# pic32_dip_breakout.net
KiCad netlist of a schematic drawn in EAGLE
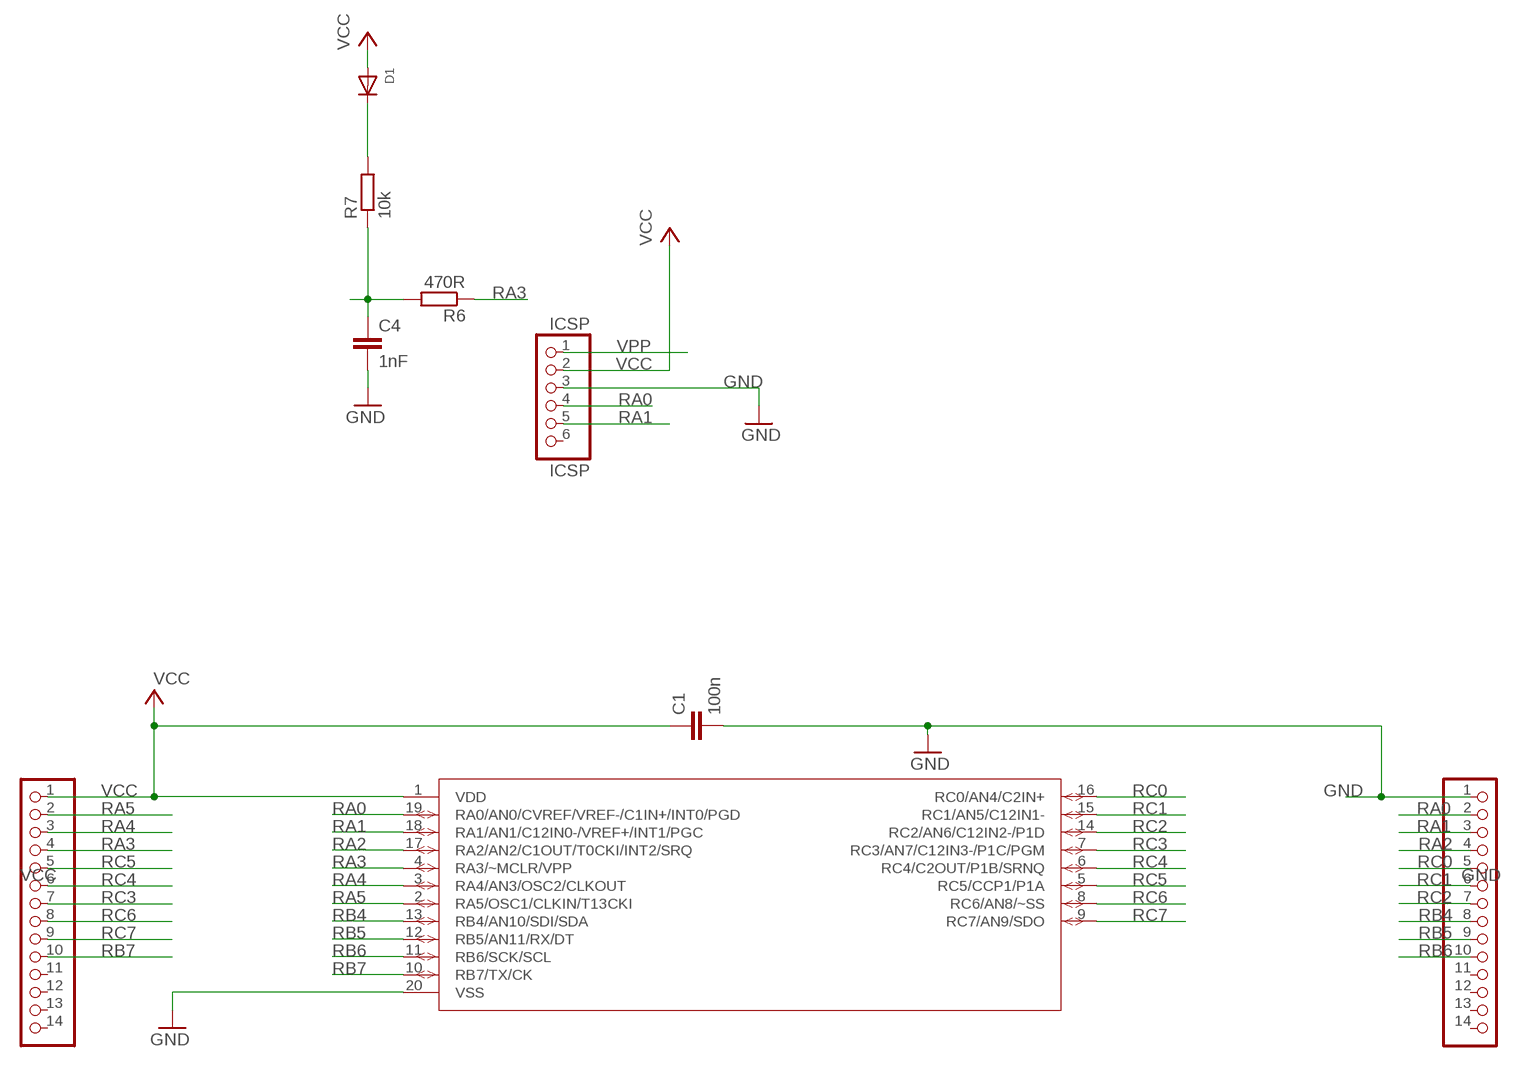
[diagram p0: schematic, sheet 1]

(export (version "E")
  (design (tool "Eeschema 10.0.6"))
  (components
    (comp (ref "C1")
      (value "100n")
      (footprint "eagle-import:C0805")
      (libsource (lib "eagle-import") (part "C-EUC0805"))
    )
    (comp (ref "C4")
      (value "1nF")
      (footprint "eagle-import:C0805")
      (libsource (lib "eagle-import") (part "resistor_C-EUC0805"))
    )
    (comp (ref "D1")
      (value "DIODESOD-323F")
      (footprint "eagle-import:SOD-323F")
      (libsource (lib "eagle-import") (part "DIODESOD-323F"))
    )
    (comp (ref "GND")
      (value "PINHD-1X14")
      (footprint "eagle-import:1X14")
      (libsource (lib "eagle-import") (part "PINHD-1X14"))
    )
    (comp (ref "ICSP")
      (value "ICSP")
      (footprint "eagle-import:1X06")
      (libsource (lib "eagle-import") (part "PINHD-1X6"))
    )
    (comp (ref "R6")
      (value "470R")
      (footprint "eagle-import:R0805")
      (libsource (lib "eagle-import") (part "R-EU_R0805"))
    )
    (comp (ref "R7")
      (value "10k")
      (footprint "eagle-import:R0805")
      (libsource (lib "eagle-import") (part "R-EU_R0805"))
    )
    (comp (ref "U$1")
      (value "PIC18F14K22-I/P")
      (footprint "eagle-import:DIP254P762X533-20")
      (fields (field (name "MPN") "PIC18F14k22-I/P"))
      (libsource (lib "eagle-import") (part "PIC18F14K22-I/P"))
    )
    (comp (ref "VCC")
      (value "PINHD-1X14")
      (footprint "eagle-import:1X14")
      (libsource (lib "eagle-import") (part "PINHD-1X14"))
    )
  )
  (nets
    (net (code "1") (name "/RA0") (class "Default")
      (node (ref "GND") (pin "2") (pinfunction "2_2") (pintype "passive"))
      (node (ref "ICSP") (pin "4") (pinfunction "4_4") (pintype "passive"))
      (node (ref "U$1") (pin "19") (pinfunction "RA0/AN0/CVREF/VREF-/C1IN+/INT0/PGD_19") (pintype "bidirectional"))
    )
    (net (code "2") (name "/RA1") (class "Default")
      (node (ref "GND") (pin "3") (pinfunction "3_3") (pintype "passive"))
      (node (ref "ICSP") (pin "5") (pinfunction "5_5") (pintype "passive"))
      (node (ref "U$1") (pin "18") (pinfunction "RA1/AN1/C12IN0-/VREF+/INT1/PGC_18") (pintype "bidirectional"))
    )
    (net (code "3") (name "/RA2") (class "Default")
      (node (ref "GND") (pin "4") (pinfunction "4_4") (pintype "passive"))
      (node (ref "U$1") (pin "17") (pinfunction "RA2/AN2/C1OUT/T0CKI/INT2/SRQ_17") (pintype "bidirectional"))
    )
    (net (code "4") (name "/RA3") (class "Default")
      (node (ref "R6") (pin "1") (pinfunction "1_1") (pintype "passive"))
      (node (ref "U$1") (pin "4") (pinfunction "RA3/~{MCLR/VPP}_4") (pintype "bidirectional"))
      (node (ref "VCC") (pin "4") (pinfunction "4_4") (pintype "passive"))
    )
    (net (code "5") (name "/RA4") (class "Default")
      (node (ref "U$1") (pin "3") (pinfunction "RA4/AN3/OSC2/CLKOUT_3") (pintype "bidirectional"))
      (node (ref "VCC") (pin "3") (pinfunction "3_3") (pintype "passive"))
    )
    (net (code "6") (name "/RA5") (class "Default")
      (node (ref "U$1") (pin "2") (pinfunction "RA5/OSC1/CLKIN/T13CKI_2") (pintype "bidirectional"))
      (node (ref "VCC") (pin "2") (pinfunction "2_2") (pintype "passive"))
    )
    (net (code "7") (name "/RB4") (class "Default")
      (node (ref "GND") (pin "8") (pinfunction "8_8") (pintype "passive"))
      (node (ref "U$1") (pin "13") (pinfunction "RB4/AN10/SDI/SDA_13") (pintype "bidirectional"))
    )
    (net (code "8") (name "/RB5") (class "Default")
      (node (ref "GND") (pin "9") (pinfunction "9_9") (pintype "passive"))
      (node (ref "U$1") (pin "12") (pinfunction "RB5/AN11/RX/DT_12") (pintype "bidirectional"))
    )
    (net (code "9") (name "/RB6") (class "Default")
      (node (ref "GND") (pin "10") (pinfunction "10_10") (pintype "passive"))
      (node (ref "U$1") (pin "11") (pinfunction "RB6/SCK/SCL_11") (pintype "bidirectional"))
    )
    (net (code "10") (name "/RB7") (class "Default")
      (node (ref "U$1") (pin "10") (pinfunction "RB7/TX/CK_10") (pintype "bidirectional"))
      (node (ref "VCC") (pin "10") (pinfunction "10_10") (pintype "passive"))
    )
    (net (code "11") (name "/RC0") (class "Default")
      (node (ref "GND") (pin "5") (pinfunction "5_5") (pintype "passive"))
      (node (ref "U$1") (pin "16") (pinfunction "RC0/AN4/C2IN+_16") (pintype "bidirectional"))
    )
    (net (code "12") (name "/RC1") (class "Default")
      (node (ref "GND") (pin "6") (pinfunction "6_6") (pintype "passive"))
      (node (ref "U$1") (pin "15") (pinfunction "RC1/AN5/C12IN1-_15") (pintype "bidirectional"))
    )
    (net (code "13") (name "/RC2") (class "Default")
      (node (ref "GND") (pin "7") (pinfunction "7_7") (pintype "passive"))
      (node (ref "U$1") (pin "14") (pinfunction "RC2/AN6/C12IN2-/P1D_14") (pintype "bidirectional"))
    )
    (net (code "14") (name "/RC3") (class "Default")
      (node (ref "U$1") (pin "7") (pinfunction "RC3/AN7/C12IN3-/P1C/PGM_7") (pintype "bidirectional"))
      (node (ref "VCC") (pin "7") (pinfunction "7_7") (pintype "passive"))
    )
    (net (code "15") (name "/RC4") (class "Default")
      (node (ref "U$1") (pin "6") (pinfunction "RC4/C2OUT/P1B/SRNQ_6") (pintype "bidirectional"))
      (node (ref "VCC") (pin "6") (pinfunction "6_6") (pintype "passive"))
    )
    (net (code "16") (name "/RC5") (class "Default")
      (node (ref "U$1") (pin "5") (pinfunction "RC5/CCP1/P1A_5") (pintype "bidirectional"))
      (node (ref "VCC") (pin "5") (pinfunction "5_5") (pintype "passive"))
    )
    (net (code "17") (name "/RC6") (class "Default")
      (node (ref "U$1") (pin "8") (pinfunction "RC6/AN8/~{SS}_8") (pintype "bidirectional"))
      (node (ref "VCC") (pin "8") (pinfunction "8_8") (pintype "passive"))
    )
    (net (code "18") (name "/RC7") (class "Default")
      (node (ref "U$1") (pin "9") (pinfunction "RC7/AN9/SDO_9") (pintype "bidirectional"))
      (node (ref "VCC") (pin "9") (pinfunction "9_9") (pintype "passive"))
    )
    (net (code "19") (name "/VPP") (class "Default")
      (node (ref "C4") (pin "1") (pinfunction "1_1") (pintype "passive"))
      (node (ref "ICSP") (pin "1") (pinfunction "1_1") (pintype "passive"))
      (node (ref "R6") (pin "2") (pinfunction "2_2") (pintype "passive"))
      (node (ref "R7") (pin "1") (pinfunction "1_1") (pintype "passive"))
    )
    (net (code "20") (name "GND") (class "Default")
      (node (ref "C1") (pin "2") (pinfunction "2_2") (pintype "passive"))
      (node (ref "C4") (pin "2") (pinfunction "2_2") (pintype "passive"))
      (node (ref "GND") (pin "1") (pinfunction "1_1") (pintype "passive"))
      (node (ref "ICSP") (pin "3") (pinfunction "3_3") (pintype "passive"))
      (node (ref "U$1") (pin "20") (pinfunction "VSS_20") (pintype "power_in"))
    )
    (net (code "21") (name "Net-(D1-PadC)") (class "Default")
      (node (ref "D1") (pin "C") (pinfunction "C_C") (pintype "passive"))
      (node (ref "R7") (pin "2") (pinfunction "2_2") (pintype "passive"))
    )
    (net (code "22") (name "VCC") (class "Default")
      (node (ref "C1") (pin "1") (pinfunction "1_1") (pintype "passive"))
      (node (ref "D1") (pin "A") (pinfunction "A_A") (pintype "passive"))
      (node (ref "ICSP") (pin "2") (pinfunction "2_2") (pintype "passive"))
      (node (ref "U$1") (pin "1") (pinfunction "VDD_1") (pintype "power_in"))
      (node (ref "VCC") (pin "1") (pinfunction "1_1") (pintype "passive"))
    )
    (net (code "23") (name "unconnected-(GND-Pad11)") (class "Default")
      (node (ref "GND") (pin "11") (pinfunction "11_11") (pintype "passive"))
    )
    (net (code "24") (name "unconnected-(GND-Pad12)") (class "Default")
      (node (ref "GND") (pin "12") (pinfunction "12_12") (pintype "passive"))
    )
    (net (code "25") (name "unconnected-(GND-Pad13)") (class "Default")
      (node (ref "GND") (pin "13") (pinfunction "13_13") (pintype "passive"))
    )
    (net (code "26") (name "unconnected-(GND-Pad14)") (class "Default")
      (node (ref "GND") (pin "14") (pinfunction "14_14") (pintype "passive"))
    )
    (net (code "27") (name "unconnected-(ICSP-Pad6)") (class "Default")
      (node (ref "ICSP") (pin "6") (pinfunction "6_6") (pintype "passive"))
    )
    (net (code "28") (name "unconnected-(VCC-Pad11)") (class "Default")
      (node (ref "VCC") (pin "11") (pinfunction "11_11") (pintype "passive"))
    )
    (net (code "29") (name "unconnected-(VCC-Pad12)") (class "Default")
      (node (ref "VCC") (pin "12") (pinfunction "12_12") (pintype "passive"))
    )
    (net (code "30") (name "unconnected-(VCC-Pad13)") (class "Default")
      (node (ref "VCC") (pin "13") (pinfunction "13_13") (pintype "passive"))
    )
    (net (code "31") (name "unconnected-(VCC-Pad14)") (class "Default")
      (node (ref "VCC") (pin "14") (pinfunction "14_14") (pintype "passive"))
    )
  )
)
